# SkyKontrol-watchdog.net
KiCad netlist of a schematic drawn in EAGLE
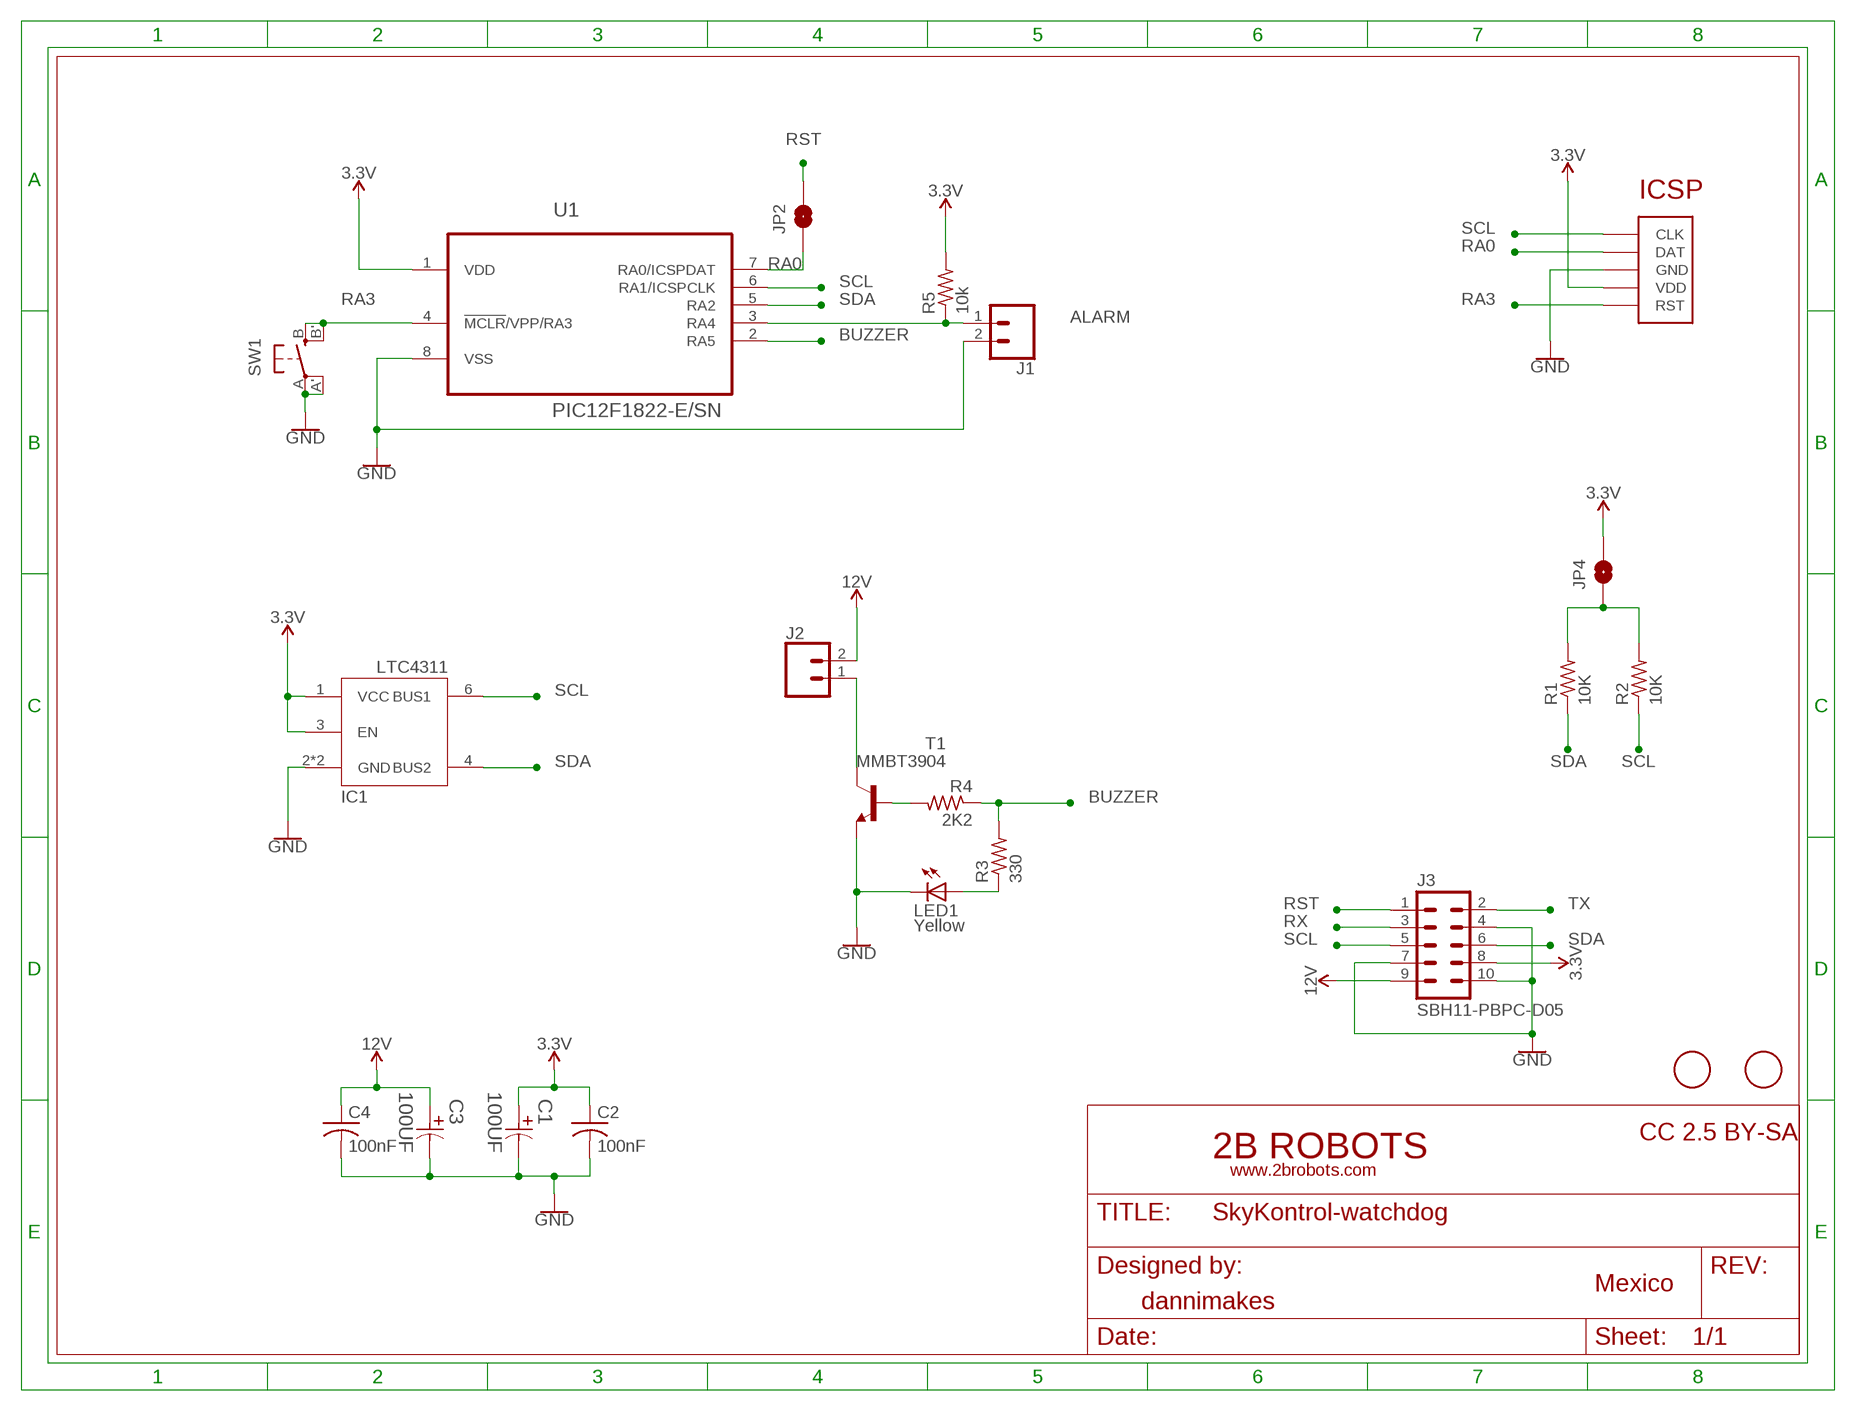
[diagram p0: schematic, sheet 1]

(export (version "E")
  (design (tool "Eeschema 10.0.6"))
  (components
    (comp (ref "C1")
      (value "100UF")
      (footprint "eagle-import:CAPAE660X800N")
      (fields (field (name "MPN") "EEE-HA1E101XP") (field (name "TOLERANCE") "±20 %"))
      (libsource (lib "eagle-import") (part "EEE--CASE-D8HA1E101XP"))
    )
    (comp (ref "C2")
      (value "100nF")
      (footprint "eagle-import:C0603K")
      (libsource (lib "eagle-import") (part "C-USC0603K"))
    )
    (comp (ref "C3")
      (value "100UF")
      (footprint "eagle-import:CAPAE660X800N")
      (fields (field (name "MPN") "EEE-HA1E101XP") (field (name "TOLERANCE") "±20 %"))
      (libsource (lib "eagle-import") (part "EEE--CASE-D8HA1E101XP"))
    )
    (comp (ref "C4")
      (value "100nF")
      (footprint "eagle-import:C0603K")
      (libsource (lib "eagle-import") (part "C-USC0603K"))
    )
    (comp (ref "IC1")
      (value "LTC4311_SC70")
      (footprint "eagle-import:SC70-6L")
      (libsource (lib "eagle-import") (part "LTC4311_SC70"))
    )
    (comp (ref "J1")
      (value "CONN_025MM")
      (footprint "eagle-import:SCREWTERMINAL-5MM-2")
      (libsource (lib "eagle-import") (part "CONN_025MM"))
    )
    (comp (ref "J2")
      (value "CONN_025MM")
      (footprint "eagle-import:SCREWTERMINAL-5MM-2")
      (libsource (lib "eagle-import") (part "CONN_025MM"))
    )
    (comp (ref "J3")
      (value "SBH11-PBPC-D05")
      (footprint "eagle-import:SBH11-PBPC-D05")
      (libsource (lib "eagle-import") (part "SBH11-PBPC-D05"))
    )
    (comp (ref "JP2")
      (value "JUMPER-SMT_2_NO_SILK")
      (footprint "eagle-import:SMT-JUMPER_2_NO_SILK")
      (libsource (lib "eagle-import") (part "JUMPER-SMT_2_NO_SILK"))
    )
    (comp (ref "JP4")
      (value "JUMPER-SMT_2_NO_SILK")
      (footprint "eagle-import:SMT-JUMPER_2_NO_SILK")
      (libsource (lib "eagle-import") (part "JUMPER-SMT_2_NO_SILK"))
    )
    (comp (ref "LED1")
      (value "Yellow")
      (footprint "eagle-import:CHIPLED_1206")
      (libsource (lib "eagle-import") (part "LEDCHIPLED_1206"))
    )
    (comp (ref "R1")
      (value "10K")
      (footprint "eagle-import:R0805")
      (libsource (lib "eagle-import") (part "R-US_R0805"))
    )
    (comp (ref "R2")
      (value "10K")
      (footprint "eagle-import:R0805")
      (libsource (lib "eagle-import") (part "R-US_R0805"))
    )
    (comp (ref "R3")
      (value "330")
      (footprint "eagle-import:R0805")
      (libsource (lib "eagle-import") (part "R-US_R0805"))
    )
    (comp (ref "R4")
      (value "2K2")
      (footprint "eagle-import:R0805")
      (libsource (lib "eagle-import") (part "R-US_R0805"))
    )
    (comp (ref "R5")
      (value "10k")
      (footprint "eagle-import:R0805")
      (libsource (lib "eagle-import") (part "R-US_R0805"))
    )
    (comp (ref "SW1")
      (value "SPST_TACT-EVQQ2")
      (footprint "eagle-import:EVQ-Q2")
      (libsource (lib "eagle-import") (part "SPST_TACT-EVQQ2"))
    )
    (comp (ref "T1")
      (value "MMBT3904")
      (footprint "eagle-import:SOT23-BEC")
      (libsource (lib "eagle-import") (part "-NPN-SOT23-BECMMBT3904LT1"))
    )
    (comp (ref "U$1")
      (value "FIDUCIAL")
      (footprint "eagle-import:FIDUCIAL_1MM")
      (libsource (lib "eagle-import") (part "FIDUCIAL"))
    )
    (comp (ref "U$2")
      (value "ICSP_POGO")
      (footprint "eagle-import:ICSP_POGO")
      (libsource (lib "eagle-import") (part "ICSP_POGO"))
    )
    (comp (ref "U$3")
      (value "FIDUCIAL")
      (footprint "eagle-import:FIDUCIAL_1MM")
      (libsource (lib "eagle-import") (part "FIDUCIAL"))
    )
    (comp (ref "U1")
      (value "PIC12F1822-E/SN")
      (footprint "eagle-import:SOIC127P600X175-8N")
      (libsource (lib "eagle-import") (part "PIC12F1822-E/SN"))
    )
  )
  (nets
    (net (code "1") (name "/ALARM") (class "Default")
      (node (ref "J1") (pin "1") (pinfunction "1_1") (pintype "passive"))
      (node (ref "R5") (pin "1") (pinfunction "1_1") (pintype "passive"))
      (node (ref "U1") (pin "3") (pinfunction "RA4_3") (pintype "bidirectional"))
    )
    (net (code "2") (name "/BUZZER") (class "Default")
      (node (ref "R3") (pin "2") (pinfunction "2_2") (pintype "passive"))
      (node (ref "R4") (pin "1") (pinfunction "1_1") (pintype "passive"))
      (node (ref "U1") (pin "2") (pinfunction "RA5_2") (pintype "bidirectional"))
    )
    (net (code "3") (name "/RA0") (class "Default")
      (node (ref "JP2") (pin "1") (pinfunction "1_1") (pintype "passive"))
      (node (ref "U$2") (pin "P$4") (pinfunction "DAT_P$4") (pintype "bidirectional"))
      (node (ref "U1") (pin "7") (pinfunction "RA0/ICSPDAT_7") (pintype "bidirectional"))
    )
    (net (code "4") (name "/RA3") (class "Default")
      (node (ref "SW1") (pin "B") (pinfunction "S_B") (pintype "passive"))
      (node (ref "SW1") (pin "B'") (pinfunction "S1_B'") (pintype "passive"))
      (node (ref "U$2") (pin "P$1") (pinfunction "RST_P$1") (pintype "bidirectional"))
      (node (ref "U1") (pin "4") (pinfunction "~{MCLR}/VPP/RA3_4") (pintype "input"))
    )
    (net (code "5") (name "/RST") (class "Default")
      (node (ref "J3") (pin "1") (pinfunction "1_1") (pintype "passive"))
      (node (ref "JP2") (pin "2") (pinfunction "2_2") (pintype "passive"))
    )
    (net (code "6") (name "/RX") (class "Default")
      (node (ref "J3") (pin "3") (pinfunction "3_3") (pintype "passive"))
    )
    (net (code "7") (name "/SCL") (class "Default")
      (node (ref "IC1") (pin "6") (pinfunction "BUS1_6") (pintype "bidirectional"))
      (node (ref "J3") (pin "5") (pinfunction "5_5") (pintype "passive"))
      (node (ref "R2") (pin "1") (pinfunction "1_1") (pintype "passive"))
      (node (ref "U$2") (pin "P$5") (pinfunction "CLK_P$5") (pintype "bidirectional"))
      (node (ref "U1") (pin "6") (pinfunction "RA1/ICSPCLK_6") (pintype "bidirectional"))
    )
    (net (code "8") (name "/SDA") (class "Default")
      (node (ref "IC1") (pin "4") (pinfunction "BUS2_4") (pintype "bidirectional"))
      (node (ref "J3") (pin "6") (pinfunction "6_6") (pintype "passive"))
      (node (ref "R1") (pin "1") (pinfunction "1_1") (pintype "passive"))
      (node (ref "U1") (pin "5") (pinfunction "RA2_5") (pintype "bidirectional"))
    )
    (net (code "9") (name "/TX") (class "Default")
      (node (ref "J3") (pin "2") (pinfunction "2_2") (pintype "passive"))
    )
    (net (code "10") (name "3.3V") (class "Default")
      (node (ref "C1") (pin "1") (pinfunction "1_1") (pintype "passive"))
      (node (ref "C2") (pin "1") (pinfunction "1_1") (pintype "passive"))
      (node (ref "IC1") (pin "1") (pinfunction "VCC_1") (pintype "power_in"))
      (node (ref "IC1") (pin "3") (pinfunction "EN_3") (pintype "input"))
      (node (ref "J3") (pin "8") (pinfunction "8_8") (pintype "passive"))
      (node (ref "JP4") (pin "2") (pinfunction "2_2") (pintype "passive"))
      (node (ref "R5") (pin "2") (pinfunction "2_2") (pintype "passive"))
      (node (ref "U$2") (pin "P$2") (pinfunction "VDD_P$2") (pintype "bidirectional"))
      (node (ref "U1") (pin "1") (pinfunction "VDD_1") (pintype "power_in"))
    )
    (net (code "11") (name "12V") (class "Default")
      (node (ref "C3") (pin "1") (pinfunction "1_1") (pintype "passive"))
      (node (ref "C4") (pin "1") (pinfunction "1_1") (pintype "passive"))
      (node (ref "J2") (pin "2") (pinfunction "2_2") (pintype "passive"))
      (node (ref "J3") (pin "9") (pinfunction "9_9") (pintype "passive"))
    )
    (net (code "12") (name "GND") (class "Default")
      (node (ref "C1") (pin "2") (pinfunction "2_2") (pintype "passive"))
      (node (ref "C2") (pin "2") (pinfunction "2_2") (pintype "passive"))
      (node (ref "C3") (pin "2") (pinfunction "2_2") (pintype "passive"))
      (node (ref "C4") (pin "2") (pinfunction "2_2") (pintype "passive"))
      (node (ref "IC1") (pin "2") (pinfunction "GND_2") (pintype "power_in"))
      (node (ref "IC1") (pin "5") (pinfunction "GND_5") (pintype "power_in"))
      (node (ref "J1") (pin "2") (pinfunction "2_2") (pintype "passive"))
      (node (ref "J3") (pin "10") (pinfunction "10_10") (pintype "passive"))
      (node (ref "J3") (pin "4") (pinfunction "4_4") (pintype "passive"))
      (node (ref "J3") (pin "7") (pinfunction "7_7") (pintype "passive"))
      (node (ref "LED1") (pin "C") (pinfunction "C_C") (pintype "passive"))
      (node (ref "SW1") (pin "A") (pinfunction "P_A") (pintype "passive"))
      (node (ref "SW1") (pin "A'") (pinfunction "P1_A'") (pintype "passive"))
      (node (ref "T1") (pin "E") (pinfunction "E_E") (pintype "passive"))
      (node (ref "U$2") (pin "P$3") (pinfunction "GND_P$3") (pintype "bidirectional"))
      (node (ref "U1") (pin "8") (pinfunction "VSS_8") (pintype "power_in"))
    )
    (net (code "13") (name "Net-(J2-Pad1)") (class "Default")
      (node (ref "J2") (pin "1") (pinfunction "1_1") (pintype "passive"))
      (node (ref "T1") (pin "C") (pinfunction "C_C") (pintype "passive"))
    )
    (net (code "14") (name "Net-(JP4-Pad1)") (class "Default")
      (node (ref "JP4") (pin "1") (pinfunction "1_1") (pintype "passive"))
      (node (ref "R1") (pin "2") (pinfunction "2_2") (pintype "passive"))
      (node (ref "R2") (pin "2") (pinfunction "2_2") (pintype "passive"))
    )
    (net (code "15") (name "Net-(LED1-PadA)") (class "Default")
      (node (ref "LED1") (pin "A") (pinfunction "A_A") (pintype "passive"))
      (node (ref "R3") (pin "1") (pinfunction "1_1") (pintype "passive"))
    )
    (net (code "16") (name "Net-(R4-Pad2)") (class "Default")
      (node (ref "R4") (pin "2") (pinfunction "2_2") (pintype "passive"))
      (node (ref "T1") (pin "B") (pinfunction "B_B") (pintype "passive"))
    )
  )
)
